# main.net
KiCad netlist of a schematic drawn in EAGLE
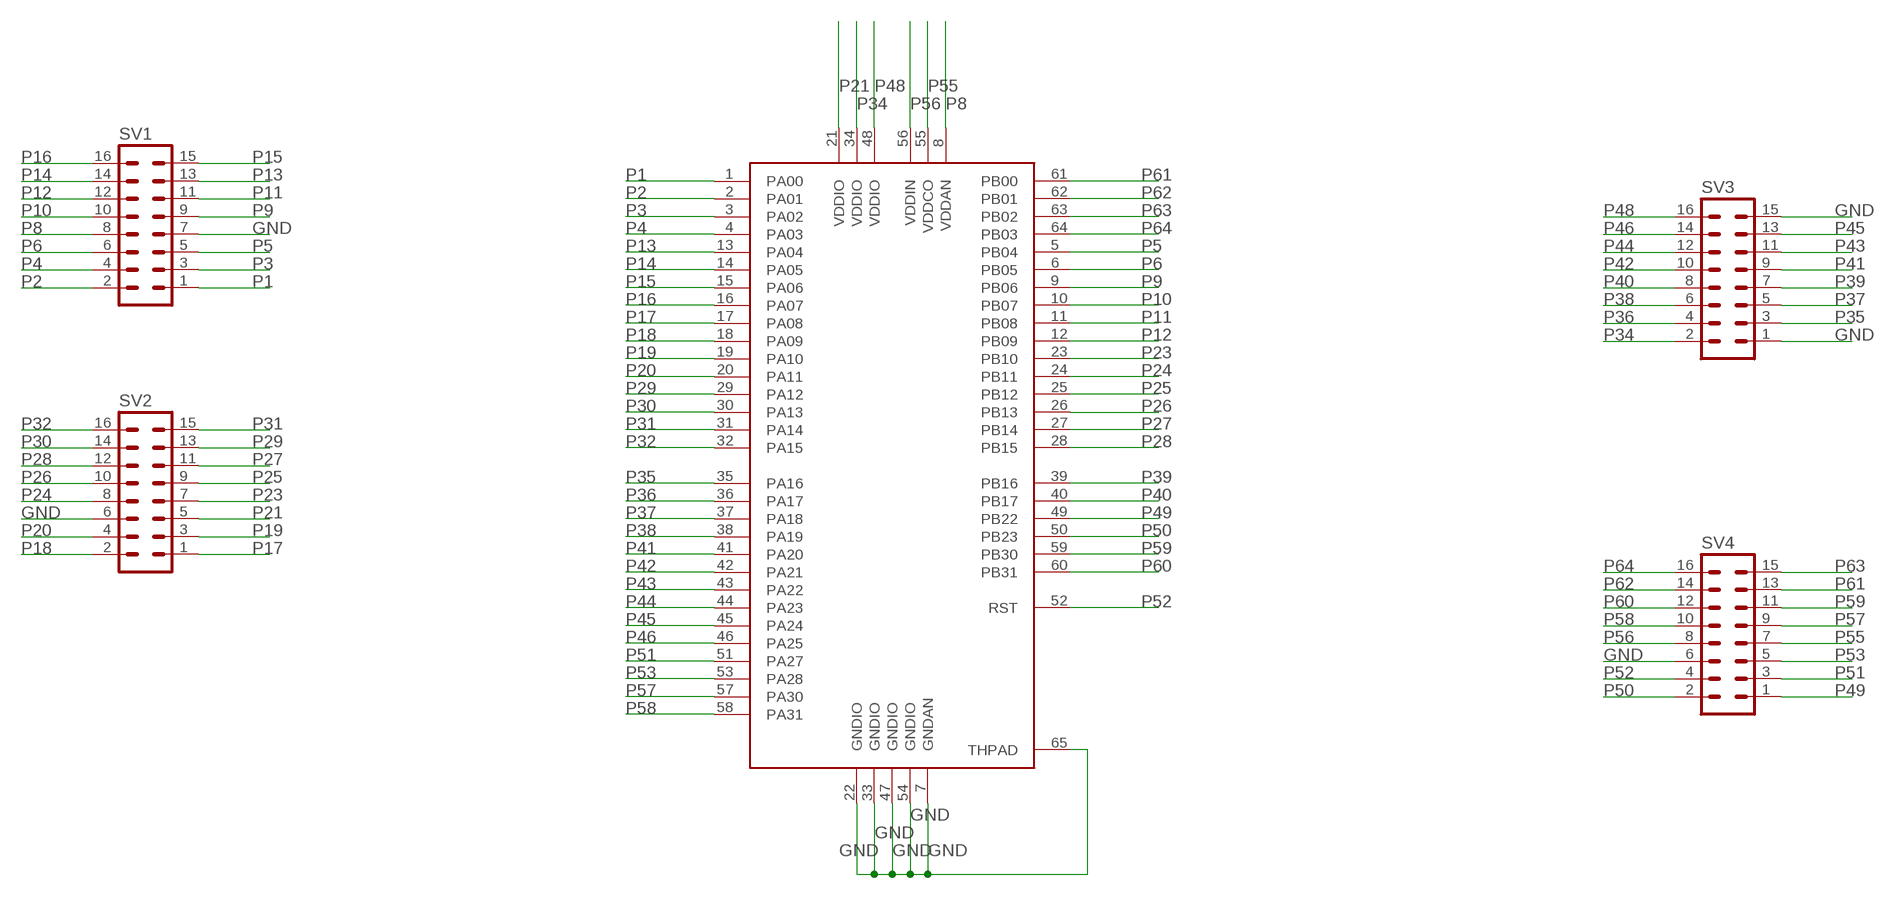
[diagram p0: schematic, sheet 1]

(export (version "E")
  (design (tool "Eeschema 10.0.6"))
  (components
    (comp (ref "SV1")
      (value "MA08-2")
      (footprint "eagle-import:MA08-2")
      (libsource (lib "eagle-import") (part "MA08-2"))
    )
    (comp (ref "SV2")
      (value "MA08-2")
      (footprint "eagle-import:MA08-2")
      (libsource (lib "eagle-import") (part "MA08-2"))
    )
    (comp (ref "SV3")
      (value "MA08-2")
      (footprint "eagle-import:MA08-2")
      (libsource (lib "eagle-import") (part "MA08-2"))
    )
    (comp (ref "SV4")
      (value "MA08-2")
      (footprint "eagle-import:MA08-2")
      (libsource (lib "eagle-import") (part "MA08-2"))
    )
    (comp (ref "U$1")
      (value "ATSAMD21J18AQFN64")
      (footprint "eagle-import:QFN50P900X900X100-65T535")
      (libsource (lib "eagle-import") (part "ATSAMD21J18AQFN64"))
    )
  )
  (nets
    (net (code "1") (name "/GND") (class "Default")
      (node (ref "SV1") (pin "7") (pinfunction "7_7") (pintype "passive"))
      (node (ref "SV2") (pin "6") (pinfunction "6_6") (pintype "passive"))
      (node (ref "SV3") (pin "1") (pinfunction "1_1") (pintype "passive"))
      (node (ref "SV3") (pin "15") (pinfunction "15_15") (pintype "passive"))
      (node (ref "SV4") (pin "6") (pinfunction "6_6") (pintype "passive"))
      (node (ref "U$1") (pin "22") (pinfunction "GNDIO_22") (pintype "bidirectional"))
      (node (ref "U$1") (pin "33") (pinfunction "GNDIO_33") (pintype "bidirectional"))
      (node (ref "U$1") (pin "47") (pinfunction "GNDIO_47") (pintype "bidirectional"))
      (node (ref "U$1") (pin "54") (pinfunction "GNDIO_54") (pintype "bidirectional"))
      (node (ref "U$1") (pin "65") (pinfunction "THPAD_65") (pintype "bidirectional"))
      (node (ref "U$1") (pin "7") (pinfunction "GNDAN_7") (pintype "bidirectional"))
    )
    (net (code "2") (name "/P1") (class "Default")
      (node (ref "SV1") (pin "1") (pinfunction "1_1") (pintype "passive"))
      (node (ref "U$1") (pin "1") (pinfunction "PA00_1") (pintype "bidirectional"))
    )
    (net (code "3") (name "/P2") (class "Default")
      (node (ref "SV1") (pin "2") (pinfunction "2_2") (pintype "passive"))
      (node (ref "U$1") (pin "2") (pinfunction "PA01_2") (pintype "bidirectional"))
    )
    (net (code "4") (name "/P3") (class "Default")
      (node (ref "SV1") (pin "3") (pinfunction "3_3") (pintype "passive"))
      (node (ref "U$1") (pin "3") (pinfunction "PA02_3") (pintype "bidirectional"))
    )
    (net (code "5") (name "/P4") (class "Default")
      (node (ref "SV1") (pin "4") (pinfunction "4_4") (pintype "passive"))
      (node (ref "U$1") (pin "4") (pinfunction "PA03_4") (pintype "bidirectional"))
    )
    (net (code "6") (name "/P5") (class "Default")
      (node (ref "SV1") (pin "5") (pinfunction "5_5") (pintype "passive"))
      (node (ref "U$1") (pin "5") (pinfunction "PB04_5") (pintype "bidirectional"))
    )
    (net (code "7") (name "/P6") (class "Default")
      (node (ref "SV1") (pin "6") (pinfunction "6_6") (pintype "passive"))
      (node (ref "U$1") (pin "6") (pinfunction "PB05_6") (pintype "bidirectional"))
    )
    (net (code "8") (name "/P8") (class "Default")
      (node (ref "SV1") (pin "8") (pinfunction "8_8") (pintype "passive"))
      (node (ref "U$1") (pin "8") (pinfunction "VDDAN_8") (pintype "bidirectional"))
    )
    (net (code "9") (name "/P9") (class "Default")
      (node (ref "SV1") (pin "9") (pinfunction "9_9") (pintype "passive"))
      (node (ref "U$1") (pin "9") (pinfunction "PB06_9") (pintype "bidirectional"))
    )
    (net (code "10") (name "/P10") (class "Default")
      (node (ref "SV1") (pin "10") (pinfunction "10_10") (pintype "passive"))
      (node (ref "U$1") (pin "10") (pinfunction "PB07_10") (pintype "bidirectional"))
    )
    (net (code "11") (name "/P11") (class "Default")
      (node (ref "SV1") (pin "11") (pinfunction "11_11") (pintype "passive"))
      (node (ref "U$1") (pin "11") (pinfunction "PB08_11") (pintype "bidirectional"))
    )
    (net (code "12") (name "/P12") (class "Default")
      (node (ref "SV1") (pin "12") (pinfunction "12_12") (pintype "passive"))
      (node (ref "U$1") (pin "12") (pinfunction "PB09_12") (pintype "bidirectional"))
    )
    (net (code "13") (name "/P13") (class "Default")
      (node (ref "SV1") (pin "13") (pinfunction "13_13") (pintype "passive"))
      (node (ref "U$1") (pin "13") (pinfunction "PA04_13") (pintype "bidirectional"))
    )
    (net (code "14") (name "/P14") (class "Default")
      (node (ref "SV1") (pin "14") (pinfunction "14_14") (pintype "passive"))
      (node (ref "U$1") (pin "14") (pinfunction "PA05_14") (pintype "bidirectional"))
    )
    (net (code "15") (name "/P15") (class "Default")
      (node (ref "SV1") (pin "15") (pinfunction "15_15") (pintype "passive"))
      (node (ref "U$1") (pin "15") (pinfunction "PA06_15") (pintype "bidirectional"))
    )
    (net (code "16") (name "/P16") (class "Default")
      (node (ref "SV1") (pin "16") (pinfunction "16_16") (pintype "passive"))
      (node (ref "U$1") (pin "16") (pinfunction "PA07_16") (pintype "bidirectional"))
    )
    (net (code "17") (name "/P17") (class "Default")
      (node (ref "SV2") (pin "1") (pinfunction "1_1") (pintype "passive"))
      (node (ref "U$1") (pin "17") (pinfunction "PA08_17") (pintype "bidirectional"))
    )
    (net (code "18") (name "/P18") (class "Default")
      (node (ref "SV2") (pin "2") (pinfunction "2_2") (pintype "passive"))
      (node (ref "U$1") (pin "18") (pinfunction "PA09_18") (pintype "bidirectional"))
    )
    (net (code "19") (name "/P19") (class "Default")
      (node (ref "SV2") (pin "3") (pinfunction "3_3") (pintype "passive"))
      (node (ref "U$1") (pin "19") (pinfunction "PA10_19") (pintype "bidirectional"))
    )
    (net (code "20") (name "/P20") (class "Default")
      (node (ref "SV2") (pin "4") (pinfunction "4_4") (pintype "passive"))
      (node (ref "U$1") (pin "20") (pinfunction "PA11_20") (pintype "bidirectional"))
    )
    (net (code "21") (name "/P21") (class "Default")
      (node (ref "SV2") (pin "5") (pinfunction "5_5") (pintype "passive"))
      (node (ref "U$1") (pin "21") (pinfunction "VDDIO_21") (pintype "bidirectional"))
    )
    (net (code "22") (name "/P23") (class "Default")
      (node (ref "SV2") (pin "7") (pinfunction "7_7") (pintype "passive"))
      (node (ref "U$1") (pin "23") (pinfunction "PB10_23") (pintype "bidirectional"))
    )
    (net (code "23") (name "/P24") (class "Default")
      (node (ref "SV2") (pin "8") (pinfunction "8_8") (pintype "passive"))
      (node (ref "U$1") (pin "24") (pinfunction "PB11_24") (pintype "bidirectional"))
    )
    (net (code "24") (name "/P25") (class "Default")
      (node (ref "SV2") (pin "9") (pinfunction "9_9") (pintype "passive"))
      (node (ref "U$1") (pin "25") (pinfunction "PB12_25") (pintype "bidirectional"))
    )
    (net (code "25") (name "/P26") (class "Default")
      (node (ref "SV2") (pin "10") (pinfunction "10_10") (pintype "passive"))
      (node (ref "U$1") (pin "26") (pinfunction "PB13_26") (pintype "bidirectional"))
    )
    (net (code "26") (name "/P27") (class "Default")
      (node (ref "SV2") (pin "11") (pinfunction "11_11") (pintype "passive"))
      (node (ref "U$1") (pin "27") (pinfunction "PB14_27") (pintype "bidirectional"))
    )
    (net (code "27") (name "/P28") (class "Default")
      (node (ref "SV2") (pin "12") (pinfunction "12_12") (pintype "passive"))
      (node (ref "U$1") (pin "28") (pinfunction "PB15_28") (pintype "bidirectional"))
    )
    (net (code "28") (name "/P29") (class "Default")
      (node (ref "SV2") (pin "13") (pinfunction "13_13") (pintype "passive"))
      (node (ref "U$1") (pin "29") (pinfunction "PA12_29") (pintype "bidirectional"))
    )
    (net (code "29") (name "/P30") (class "Default")
      (node (ref "SV2") (pin "14") (pinfunction "14_14") (pintype "passive"))
      (node (ref "U$1") (pin "30") (pinfunction "PA13_30") (pintype "bidirectional"))
    )
    (net (code "30") (name "/P31") (class "Default")
      (node (ref "SV2") (pin "15") (pinfunction "15_15") (pintype "passive"))
      (node (ref "U$1") (pin "31") (pinfunction "PA14_31") (pintype "bidirectional"))
    )
    (net (code "31") (name "/P32") (class "Default")
      (node (ref "SV2") (pin "16") (pinfunction "16_16") (pintype "passive"))
      (node (ref "U$1") (pin "32") (pinfunction "PA15_32") (pintype "bidirectional"))
    )
    (net (code "32") (name "/P34") (class "Default")
      (node (ref "SV3") (pin "2") (pinfunction "2_2") (pintype "passive"))
      (node (ref "U$1") (pin "34") (pinfunction "VDDIO_34") (pintype "bidirectional"))
    )
    (net (code "33") (name "/P35") (class "Default")
      (node (ref "SV3") (pin "3") (pinfunction "3_3") (pintype "passive"))
      (node (ref "U$1") (pin "35") (pinfunction "PA16_35") (pintype "bidirectional"))
    )
    (net (code "34") (name "/P36") (class "Default")
      (node (ref "SV3") (pin "4") (pinfunction "4_4") (pintype "passive"))
      (node (ref "U$1") (pin "36") (pinfunction "PA17_36") (pintype "bidirectional"))
    )
    (net (code "35") (name "/P37") (class "Default")
      (node (ref "SV3") (pin "5") (pinfunction "5_5") (pintype "passive"))
      (node (ref "U$1") (pin "37") (pinfunction "PA18_37") (pintype "bidirectional"))
    )
    (net (code "36") (name "/P38") (class "Default")
      (node (ref "SV3") (pin "6") (pinfunction "6_6") (pintype "passive"))
      (node (ref "U$1") (pin "38") (pinfunction "PA19_38") (pintype "bidirectional"))
    )
    (net (code "37") (name "/P39") (class "Default")
      (node (ref "SV3") (pin "7") (pinfunction "7_7") (pintype "passive"))
      (node (ref "U$1") (pin "39") (pinfunction "PB16_39") (pintype "bidirectional"))
    )
    (net (code "38") (name "/P40") (class "Default")
      (node (ref "SV3") (pin "8") (pinfunction "8_8") (pintype "passive"))
      (node (ref "U$1") (pin "40") (pinfunction "PB17_40") (pintype "bidirectional"))
    )
    (net (code "39") (name "/P41") (class "Default")
      (node (ref "SV3") (pin "9") (pinfunction "9_9") (pintype "passive"))
      (node (ref "U$1") (pin "41") (pinfunction "PA20_41") (pintype "bidirectional"))
    )
    (net (code "40") (name "/P42") (class "Default")
      (node (ref "SV3") (pin "10") (pinfunction "10_10") (pintype "passive"))
      (node (ref "U$1") (pin "42") (pinfunction "PA21_42") (pintype "bidirectional"))
    )
    (net (code "41") (name "/P43") (class "Default")
      (node (ref "SV3") (pin "11") (pinfunction "11_11") (pintype "passive"))
      (node (ref "U$1") (pin "43") (pinfunction "PA22_43") (pintype "bidirectional"))
    )
    (net (code "42") (name "/P44") (class "Default")
      (node (ref "SV3") (pin "12") (pinfunction "12_12") (pintype "passive"))
      (node (ref "U$1") (pin "44") (pinfunction "PA23_44") (pintype "bidirectional"))
    )
    (net (code "43") (name "/P45") (class "Default")
      (node (ref "SV3") (pin "13") (pinfunction "13_13") (pintype "passive"))
      (node (ref "U$1") (pin "45") (pinfunction "PA24_45") (pintype "bidirectional"))
    )
    (net (code "44") (name "/P46") (class "Default")
      (node (ref "SV3") (pin "14") (pinfunction "14_14") (pintype "passive"))
      (node (ref "U$1") (pin "46") (pinfunction "PA25_46") (pintype "bidirectional"))
    )
    (net (code "45") (name "/P48") (class "Default")
      (node (ref "SV3") (pin "16") (pinfunction "16_16") (pintype "passive"))
      (node (ref "U$1") (pin "48") (pinfunction "VDDIO_48") (pintype "bidirectional"))
    )
    (net (code "46") (name "/P49") (class "Default")
      (node (ref "SV4") (pin "1") (pinfunction "1_1") (pintype "passive"))
      (node (ref "U$1") (pin "49") (pinfunction "PB22_49") (pintype "bidirectional"))
    )
    (net (code "47") (name "/P50") (class "Default")
      (node (ref "SV4") (pin "2") (pinfunction "2_2") (pintype "passive"))
      (node (ref "U$1") (pin "50") (pinfunction "PB23_50") (pintype "bidirectional"))
    )
    (net (code "48") (name "/P51") (class "Default")
      (node (ref "SV4") (pin "3") (pinfunction "3_3") (pintype "passive"))
      (node (ref "U$1") (pin "51") (pinfunction "PA27_51") (pintype "bidirectional"))
    )
    (net (code "49") (name "/P52") (class "Default")
      (node (ref "SV4") (pin "4") (pinfunction "4_4") (pintype "passive"))
      (node (ref "U$1") (pin "52") (pinfunction "RST_52") (pintype "bidirectional"))
    )
    (net (code "50") (name "/P53") (class "Default")
      (node (ref "SV4") (pin "5") (pinfunction "5_5") (pintype "passive"))
      (node (ref "U$1") (pin "53") (pinfunction "PA28_53") (pintype "bidirectional"))
    )
    (net (code "51") (name "/P55") (class "Default")
      (node (ref "SV4") (pin "7") (pinfunction "7_7") (pintype "passive"))
      (node (ref "U$1") (pin "55") (pinfunction "VDDCO_55") (pintype "bidirectional"))
    )
    (net (code "52") (name "/P56") (class "Default")
      (node (ref "SV4") (pin "8") (pinfunction "8_8") (pintype "passive"))
      (node (ref "U$1") (pin "56") (pinfunction "VDDIN_56") (pintype "bidirectional"))
    )
    (net (code "53") (name "/P57") (class "Default")
      (node (ref "SV4") (pin "9") (pinfunction "9_9") (pintype "passive"))
      (node (ref "U$1") (pin "57") (pinfunction "PA30_57") (pintype "bidirectional"))
    )
    (net (code "54") (name "/P58") (class "Default")
      (node (ref "SV4") (pin "10") (pinfunction "10_10") (pintype "passive"))
      (node (ref "U$1") (pin "58") (pinfunction "PA31_58") (pintype "bidirectional"))
    )
    (net (code "55") (name "/P59") (class "Default")
      (node (ref "SV4") (pin "11") (pinfunction "11_11") (pintype "passive"))
      (node (ref "U$1") (pin "59") (pinfunction "PB30_59") (pintype "bidirectional"))
    )
    (net (code "56") (name "/P60") (class "Default")
      (node (ref "SV4") (pin "12") (pinfunction "12_12") (pintype "passive"))
      (node (ref "U$1") (pin "60") (pinfunction "PB31_60") (pintype "bidirectional"))
    )
    (net (code "57") (name "/P61") (class "Default")
      (node (ref "SV4") (pin "13") (pinfunction "13_13") (pintype "passive"))
      (node (ref "U$1") (pin "61") (pinfunction "PB00_61") (pintype "bidirectional"))
    )
    (net (code "58") (name "/P62") (class "Default")
      (node (ref "SV4") (pin "14") (pinfunction "14_14") (pintype "passive"))
      (node (ref "U$1") (pin "62") (pinfunction "PB01_62") (pintype "bidirectional"))
    )
    (net (code "59") (name "/P63") (class "Default")
      (node (ref "SV4") (pin "15") (pinfunction "15_15") (pintype "passive"))
      (node (ref "U$1") (pin "63") (pinfunction "PB02_63") (pintype "bidirectional"))
    )
    (net (code "60") (name "/P64") (class "Default")
      (node (ref "SV4") (pin "16") (pinfunction "16_16") (pintype "passive"))
      (node (ref "U$1") (pin "64") (pinfunction "PB03_64") (pintype "bidirectional"))
    )
  )
)
